# PA_PShifter_R00.net
KiCad netlist of a schematic drawn in Altium Designer
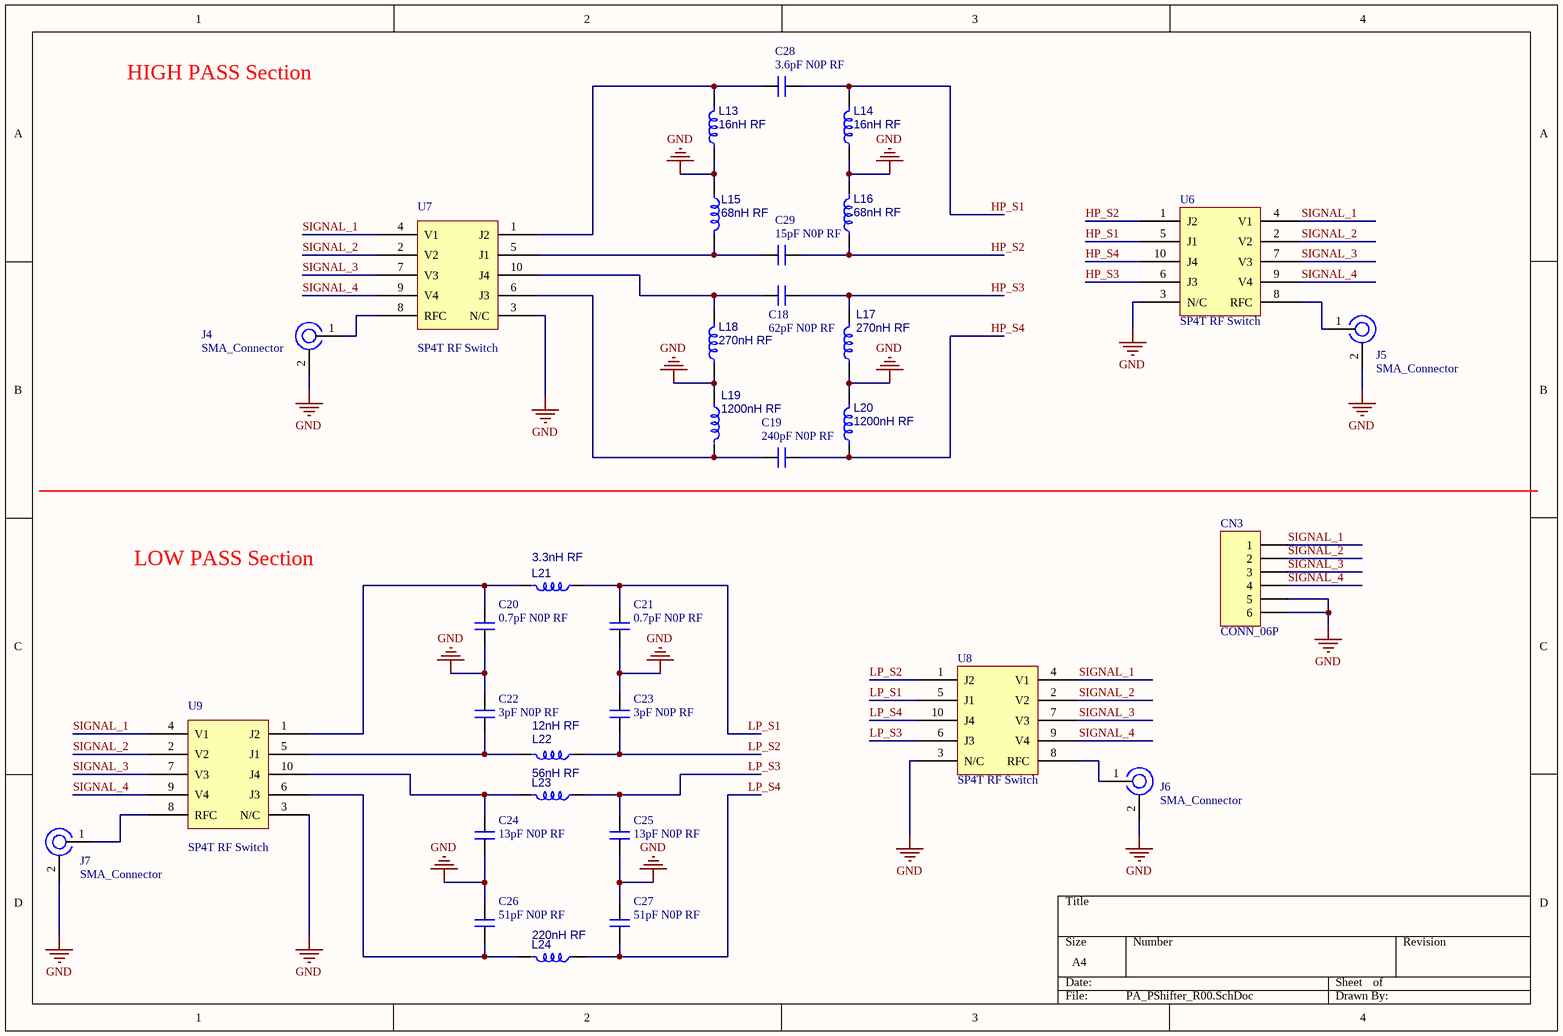
[diagram p0: PA_PShifter_R00.SchDoc]

(export (version "E")
  (design (tool "Eeschema 10.0.6"))
  (components
    (comp (ref "C18")
      (value "62pF N0P RF")
      (footprint "C_0603")
      (libsource (lib "SchLib_PocketAnalyzer") (part "Ceramic Cap"))
    )
    (comp (ref "C19")
      (value "240pF N0P RF")
      (footprint "C_0603")
      (libsource (lib "SchLib_PocketAnalyzer") (part "Ceramic Cap"))
    )
    (comp (ref "C20")
      (value "0.7pF N0P RF")
      (footprint "C_0603")
      (libsource (lib "SchLib_PocketAnalyzer") (part "Ceramic Cap"))
    )
    (comp (ref "C21")
      (value "0.7pF N0P RF")
      (footprint "C_0603")
      (libsource (lib "SchLib_PocketAnalyzer") (part "Ceramic Cap"))
    )
    (comp (ref "C22")
      (value "3pF N0P RF")
      (footprint "C_0603")
      (libsource (lib "SchLib_PocketAnalyzer") (part "Ceramic Cap"))
    )
    (comp (ref "C23")
      (value "3pF N0P RF")
      (footprint "C_0603")
      (libsource (lib "SchLib_PocketAnalyzer") (part "Ceramic Cap"))
    )
    (comp (ref "C24")
      (value "13pF N0P RF")
      (footprint "C_0603")
      (libsource (lib "SchLib_PocketAnalyzer") (part "Ceramic Cap"))
    )
    (comp (ref "C25")
      (value "13pF N0P RF")
      (footprint "C_0603")
      (libsource (lib "SchLib_PocketAnalyzer") (part "Ceramic Cap"))
    )
    (comp (ref "C26")
      (value "51pF N0P RF")
      (footprint "C_0603")
      (libsource (lib "SchLib_PocketAnalyzer") (part "Ceramic Cap"))
    )
    (comp (ref "C27")
      (value "51pF N0P RF")
      (footprint "C_0603")
      (libsource (lib "SchLib_PocketAnalyzer") (part "Ceramic Cap"))
    )
    (comp (ref "C28")
      (value "3.6pF N0P RF")
      (footprint "C_0603")
      (libsource (lib "SchLib_PocketAnalyzer") (part "Ceramic Cap"))
    )
    (comp (ref "C29")
      (value "15pF N0P RF")
      (footprint "C_0603")
      (libsource (lib "SchLib_PocketAnalyzer") (part "Ceramic Cap"))
    )
    (comp (ref "CN3")
      (value "CONN_06P")
      (footprint "Header_M_2x3_0.1\"")
      (description "Connector Generic 4 Vias")
      (libsource (lib "SchLib_PocketAnalyzer") (part "CONN_06P"))
    )
    (comp (ref "J4")
      (value "SMA_Connector")
      (footprint "SMA_Connector")
      (description "Connector SMA")
      (libsource (lib "SchLib_PocketAnalyzer") (part "SMA_Connector"))
    )
    (comp (ref "J5")
      (value "SMA_Connector")
      (footprint "SMA_Connector")
      (description "Connector SMA")
      (libsource (lib "") (part "SMA_Connector_1"))
    )
    (comp (ref "J6")
      (value "SMA_Connector")
      (footprint "SMA_Connector")
      (description "Connector SMA")
      (libsource (lib "") (part "SMA_Connector_1"))
    )
    (comp (ref "J7")
      (value "SMA_Connector")
      (footprint "SMA_Connector")
      (description "Connector SMA")
      (libsource (lib "SchLib_PocketAnalyzer") (part "SMA_Connector"))
    )
    (comp (ref "L13")
      (value "16nH RF")
      (footprint "L_0603")
      (description "CHIP inductor")
      (libsource (lib "SchLib_PocketAnalyzer") (part "Inductor Chip"))
    )
    (comp (ref "L14")
      (value "16nH RF")
      (footprint "L_0603")
      (description "CHIP inductor")
      (libsource (lib "SchLib_PocketAnalyzer") (part "Inductor Chip"))
    )
    (comp (ref "L15")
      (value "68nH RF")
      (footprint "L_0603")
      (description "CHIP inductor")
      (libsource (lib "SchLib_PocketAnalyzer") (part "Inductor Chip"))
    )
    (comp (ref "L16")
      (value "68nH RF")
      (footprint "L_0603")
      (description "CHIP inductor")
      (libsource (lib "SchLib_PocketAnalyzer") (part "Inductor Chip"))
    )
    (comp (ref "L17")
      (value "270nH RF")
      (footprint "L_0603")
      (description "CHIP inductor")
      (libsource (lib "SchLib_PocketAnalyzer") (part "Inductor Chip"))
    )
    (comp (ref "L18")
      (value "270nH RF")
      (footprint "L_0603")
      (description "CHIP inductor")
      (libsource (lib "SchLib_PocketAnalyzer") (part "Inductor Chip"))
    )
    (comp (ref "L19")
      (value "1200nH RF")
      (footprint "L_0805")
      (description "CHIP inductor")
      (libsource (lib "SchLib_PocketAnalyzer") (part "Inductor Chip"))
    )
    (comp (ref "L20")
      (value "1200nH RF")
      (footprint "L_0805")
      (description "CHIP inductor")
      (libsource (lib "SchLib_PocketAnalyzer") (part "Inductor Chip"))
    )
    (comp (ref "L21")
      (value "3.3nH RF")
      (footprint "L_0603")
      (description "CHIP inductor")
      (libsource (lib "SchLib_PocketAnalyzer") (part "Inductor Chip"))
    )
    (comp (ref "L22")
      (value "12nH RF")
      (footprint "L_0603")
      (description "CHIP inductor")
      (libsource (lib "SchLib_PocketAnalyzer") (part "Inductor Chip"))
    )
    (comp (ref "L23")
      (value "56nH RF")
      (footprint "L_0603")
      (description "CHIP inductor")
      (libsource (lib "SchLib_PocketAnalyzer") (part "Inductor Chip"))
    )
    (comp (ref "L24")
      (value "220nH RF")
      (footprint "L_0603")
      (description "CHIP inductor")
      (libsource (lib "SchLib_PocketAnalyzer") (part "Inductor Chip"))
    )
    (comp (ref "U6")
      (value "SP4T RF Switch")
      (footprint "SP4T Switch RF")
      (description "SKY13322-375LF")
      (libsource (lib "SchLib_PocketAnalyzer") (part "SP4T RF Switch"))
    )
    (comp (ref "U7")
      (value "SP4T RF Switch")
      (footprint "SP4T Switch RF")
      (description "SKY13322-375LF")
      (libsource (lib "") (part "SP4T RF Switch_1"))
    )
    (comp (ref "U8")
      (value "SP4T RF Switch")
      (footprint "SP4T Switch RF")
      (description "SKY13322-375LF")
      (libsource (lib "SchLib_PocketAnalyzer") (part "SP4T RF Switch"))
    )
    (comp (ref "U9")
      (value "SP4T RF Switch")
      (footprint "SP4T Switch RF")
      (description "SKY13322-375LF")
      (libsource (lib "") (part "SP4T RF Switch_1"))
    )
  )
  (nets
    (net (code "1") (name "/HP_S1") (class "Default")
      (node (ref "C28") (pin "2") (pintype "passive"))
      (node (ref "L14") (pin "2") (pinfunction "2_2") (pintype "passive"))
      (node (ref "U6") (pin "5") (pinfunction "J1_5") (pintype "passive"))
    )
    (net (code "2") (name "/HP_S2") (class "Default")
      (node (ref "C29") (pin "2") (pintype "passive"))
      (node (ref "L16") (pin "1") (pinfunction "1_1") (pintype "passive"))
      (node (ref "U6") (pin "1") (pinfunction "J2_1") (pintype "passive"))
    )
    (net (code "3") (name "/HP_S3") (class "Default")
      (node (ref "C18") (pin "2") (pintype "passive"))
      (node (ref "L17") (pin "2") (pinfunction "2_2") (pintype "passive"))
      (node (ref "U6") (pin "6") (pinfunction "J3_6") (pintype "passive"))
    )
    (net (code "4") (name "/HP_S4") (class "Default")
      (node (ref "C19") (pin "2") (pintype "passive"))
      (node (ref "L20") (pin "1") (pinfunction "1_1") (pintype "passive"))
      (node (ref "U6") (pin "10") (pinfunction "J4_10") (pintype "passive"))
    )
    (net (code "5") (name "/LP_S1") (class "Default")
      (node (ref "C21") (pin "2") (pintype "passive"))
      (node (ref "L21") (pin "1") (pinfunction "1_1") (pintype "passive"))
      (node (ref "U8") (pin "5") (pinfunction "J1_5") (pintype "passive"))
    )
    (net (code "6") (name "/LP_S2") (class "Default")
      (node (ref "C23") (pin "1") (pintype "passive"))
      (node (ref "L22") (pin "1") (pinfunction "1_1") (pintype "passive"))
      (node (ref "U8") (pin "1") (pinfunction "J2_1") (pintype "passive"))
    )
    (net (code "7") (name "/LP_S3") (class "Default")
      (node (ref "C25") (pin "2") (pintype "passive"))
      (node (ref "L23") (pin "1") (pinfunction "1_1") (pintype "passive"))
      (node (ref "U8") (pin "6") (pinfunction "J3_6") (pintype "passive"))
    )
    (net (code "8") (name "/LP_S4") (class "Default")
      (node (ref "C27") (pin "1") (pintype "passive"))
      (node (ref "L24") (pin "1") (pinfunction "1_1") (pintype "passive"))
      (node (ref "U8") (pin "10") (pinfunction "J4_10") (pintype "passive"))
    )
    (net (code "9") (name "/SIGNAL_1") (class "Default")
      (node (ref "CN3") (pin "1") (pinfunction "1_1") (pintype "passive"))
      (node (ref "U6") (pin "4") (pinfunction "V1_4") (pintype "passive"))
      (node (ref "U7") (pin "4") (pinfunction "V1_4") (pintype "passive"))
      (node (ref "U8") (pin "4") (pinfunction "V1_4") (pintype "passive"))
      (node (ref "U9") (pin "4") (pinfunction "V1_4") (pintype "passive"))
    )
    (net (code "10") (name "/SIGNAL_2") (class "Default")
      (node (ref "CN3") (pin "2") (pinfunction "2_2") (pintype "passive"))
      (node (ref "U6") (pin "2") (pinfunction "V2_2") (pintype "passive"))
      (node (ref "U7") (pin "2") (pinfunction "V2_2") (pintype "passive"))
      (node (ref "U8") (pin "2") (pinfunction "V2_2") (pintype "passive"))
      (node (ref "U9") (pin "2") (pinfunction "V2_2") (pintype "passive"))
    )
    (net (code "11") (name "/SIGNAL_3") (class "Default")
      (node (ref "CN3") (pin "3") (pinfunction "3_3") (pintype "passive"))
      (node (ref "U6") (pin "7") (pinfunction "V3_7") (pintype "passive"))
      (node (ref "U7") (pin "7") (pinfunction "V3_7") (pintype "passive"))
      (node (ref "U8") (pin "7") (pinfunction "V3_7") (pintype "passive"))
      (node (ref "U9") (pin "7") (pinfunction "V3_7") (pintype "passive"))
    )
    (net (code "12") (name "/SIGNAL_4") (class "Default")
      (node (ref "CN3") (pin "4") (pinfunction "4_4") (pintype "passive"))
      (node (ref "U6") (pin "9") (pinfunction "V4_9") (pintype "passive"))
      (node (ref "U7") (pin "9") (pinfunction "V4_9") (pintype "passive"))
      (node (ref "U8") (pin "9") (pinfunction "V4_9") (pintype "passive"))
      (node (ref "U9") (pin "9") (pinfunction "V4_9") (pintype "passive"))
    )
    (net (code "13") (name "GND") (class "Default")
      (node (ref "C20") (pin "1") (pintype "passive"))
      (node (ref "C21") (pin "1") (pintype "passive"))
      (node (ref "C22") (pin "2") (pintype "passive"))
      (node (ref "C23") (pin "2") (pintype "passive"))
      (node (ref "C24") (pin "1") (pintype "passive"))
      (node (ref "C25") (pin "1") (pintype "passive"))
      (node (ref "C26") (pin "2") (pintype "passive"))
      (node (ref "C27") (pin "2") (pintype "passive"))
      (node (ref "CN3") (pin "5") (pinfunction "5_5") (pintype "passive"))
      (node (ref "CN3") (pin "6") (pinfunction "6_6") (pintype "passive"))
      (node (ref "J4") (pin "2") (pinfunction "2_2") (pintype "passive"))
      (node (ref "J5") (pin "2") (pinfunction "2_2") (pintype "passive"))
      (node (ref "J6") (pin "2") (pinfunction "2_2") (pintype "passive"))
      (node (ref "J7") (pin "2") (pinfunction "2_2") (pintype "passive"))
      (node (ref "L13") (pin "1") (pinfunction "1_1") (pintype "passive"))
      (node (ref "L14") (pin "1") (pinfunction "1_1") (pintype "passive"))
      (node (ref "L15") (pin "1") (pinfunction "1_1") (pintype "passive"))
      (node (ref "L16") (pin "2") (pinfunction "2_2") (pintype "passive"))
      (node (ref "L17") (pin "1") (pinfunction "1_1") (pintype "passive"))
      (node (ref "L18") (pin "1") (pinfunction "1_1") (pintype "passive"))
      (node (ref "L19") (pin "1") (pinfunction "1_1") (pintype "passive"))
      (node (ref "L20") (pin "2") (pinfunction "2_2") (pintype "passive"))
      (node (ref "U6") (pin "3") (pinfunction "N/C_3") (pintype "passive"))
      (node (ref "U7") (pin "3") (pinfunction "N/C_3") (pintype "passive"))
      (node (ref "U8") (pin "3") (pinfunction "N/C_3") (pintype "passive"))
      (node (ref "U9") (pin "3") (pinfunction "N/C_3") (pintype "passive"))
    )
    (net (code "14") (name "Net-(U6-RFC)") (class "Default")
      (node (ref "J5") (pin "1") (pinfunction "1_1") (pintype "passive"))
      (node (ref "U6") (pin "8") (pinfunction "RFC_8") (pintype "passive"))
    )
    (net (code "15") (name "Net-(U7-J1)") (class "Default")
      (node (ref "C29") (pin "1") (pintype "passive"))
      (node (ref "L15") (pin "2") (pinfunction "2_2") (pintype "passive"))
      (node (ref "U7") (pin "5") (pinfunction "J1_5") (pintype "passive"))
    )
    (net (code "16") (name "Net-(U7-J2)") (class "Default")
      (node (ref "C28") (pin "1") (pintype "passive"))
      (node (ref "L13") (pin "2") (pinfunction "2_2") (pintype "passive"))
      (node (ref "U7") (pin "1") (pinfunction "J2_1") (pintype "passive"))
    )
    (net (code "17") (name "Net-(U7-J3)") (class "Default")
      (node (ref "C19") (pin "1") (pintype "passive"))
      (node (ref "L19") (pin "2") (pinfunction "2_2") (pintype "passive"))
      (node (ref "U7") (pin "6") (pinfunction "J3_6") (pintype "passive"))
    )
    (net (code "18") (name "Net-(U7-J4)") (class "Default")
      (node (ref "C18") (pin "1") (pintype "passive"))
      (node (ref "L18") (pin "2") (pinfunction "2_2") (pintype "passive"))
      (node (ref "U7") (pin "10") (pinfunction "J4_10") (pintype "passive"))
    )
    (net (code "19") (name "Net-(U7-RFC)") (class "Default")
      (node (ref "J4") (pin "1") (pinfunction "1_1") (pintype "passive"))
      (node (ref "U7") (pin "8") (pinfunction "RFC_8") (pintype "passive"))
    )
    (net (code "20") (name "Net-(U8-RFC)") (class "Default")
      (node (ref "J6") (pin "1") (pinfunction "1_1") (pintype "passive"))
      (node (ref "U8") (pin "8") (pinfunction "RFC_8") (pintype "passive"))
    )
    (net (code "21") (name "Net-(U9-J1)") (class "Default")
      (node (ref "C22") (pin "1") (pintype "passive"))
      (node (ref "L22") (pin "2") (pinfunction "2_2") (pintype "passive"))
      (node (ref "U9") (pin "5") (pinfunction "J1_5") (pintype "passive"))
    )
    (net (code "22") (name "Net-(U9-J2)") (class "Default")
      (node (ref "C20") (pin "2") (pintype "passive"))
      (node (ref "L21") (pin "2") (pinfunction "2_2") (pintype "passive"))
      (node (ref "U9") (pin "1") (pinfunction "J2_1") (pintype "passive"))
    )
    (net (code "23") (name "Net-(U9-J3)") (class "Default")
      (node (ref "C26") (pin "1") (pintype "passive"))
      (node (ref "L24") (pin "2") (pinfunction "2_2") (pintype "passive"))
      (node (ref "U9") (pin "6") (pinfunction "J3_6") (pintype "passive"))
    )
    (net (code "24") (name "Net-(U9-J4)") (class "Default")
      (node (ref "C24") (pin "2") (pintype "passive"))
      (node (ref "L23") (pin "2") (pinfunction "2_2") (pintype "passive"))
      (node (ref "U9") (pin "10") (pinfunction "J4_10") (pintype "passive"))
    )
    (net (code "25") (name "Net-(U9-RFC)") (class "Default")
      (node (ref "J7") (pin "1") (pinfunction "1_1") (pintype "passive"))
      (node (ref "U9") (pin "8") (pinfunction "RFC_8") (pintype "passive"))
    )
  )
)
